# smile.net
KiCad netlist of a schematic drawn in EAGLE
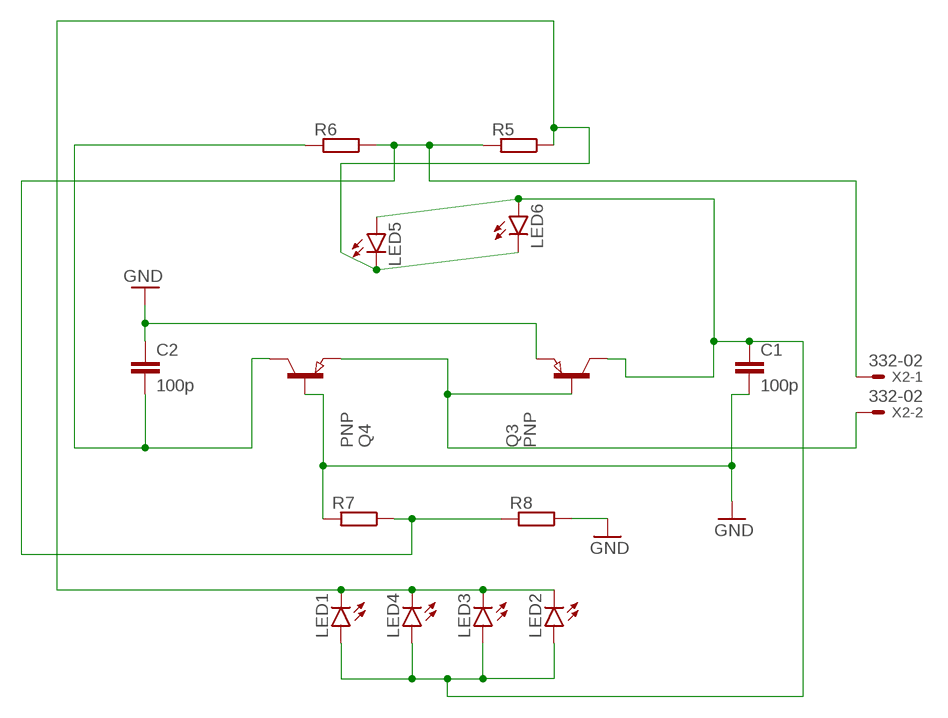
[diagram p0: schematic, sheet 1]

(export (version "E")
  (design (tool "Eeschema 10.0.6"))
  (components
    (comp (ref "C1")
      (value "100p")
      (footprint "eagle-import:C0805")
      (libsource (lib "eagle-import") (part "C-EUC0805"))
    )
    (comp (ref "C2")
      (value "100p")
      (footprint "eagle-import:C0805")
      (libsource (lib "eagle-import") (part "C-EUC0805"))
    )
    (comp (ref "LED1")
      (value "LEDCHIPLED_1206")
      (footprint "eagle-import:CHIPLED_1206")
      (libsource (lib "eagle-import") (part "LEDCHIPLED_1206"))
    )
    (comp (ref "LED2")
      (value "LEDCHIPLED_1206")
      (footprint "eagle-import:CHIPLED_1206")
      (libsource (lib "eagle-import") (part "LEDCHIPLED_1206"))
    )
    (comp (ref "LED3")
      (value "LEDCHIPLED_1206")
      (footprint "eagle-import:CHIPLED_1206")
      (libsource (lib "eagle-import") (part "LEDCHIPLED_1206"))
    )
    (comp (ref "LED4")
      (value "LEDCHIPLED_1206")
      (footprint "eagle-import:CHIPLED_1206")
      (libsource (lib "eagle-import") (part "LEDCHIPLED_1206"))
    )
    (comp (ref "LED5")
      (value "LEDCHIPLED_1206")
      (footprint "eagle-import:CHIPLED_1206")
      (libsource (lib "eagle-import") (part "LEDCHIPLED_1206"))
    )
    (comp (ref "LED6")
      (value "LEDCHIPLED_1206")
      (footprint "eagle-import:CHIPLED_1206")
      (libsource (lib "eagle-import") (part "LEDCHIPLED_1206"))
    )
    (comp (ref "Q3")
      (value "PNP")
      (footprint "eagle-import:SOT23")
      (libsource (lib "eagle-import") (part "PNP-TRANSISTOR_SOT23"))
    )
    (comp (ref "Q4")
      (value "PNP")
      (footprint "eagle-import:SOT23")
      (libsource (lib "eagle-import") (part "PNP-TRANSISTOR_SOT23"))
    )
    (comp (ref "R5")
      (value "SMK")
      (footprint "eagle-import:SMK")
      (libsource (lib "eagle-import") (part "SMK"))
    )
    (comp (ref "R6")
      (value "SMK")
      (footprint "eagle-import:SMK")
      (libsource (lib "eagle-import") (part "SMK"))
    )
    (comp (ref "R7")
      (value "SMK")
      (footprint "eagle-import:SMK")
      (libsource (lib "eagle-import") (part "SMK"))
    )
    (comp (ref "R8")
      (value "SMK")
      (footprint "eagle-import:SMK")
      (libsource (lib "eagle-import") (part "SMK"))
    )
    (comp (ref "X2")
      (value "332-02")
      (footprint "eagle-import:332-02")
      (libsource (lib "eagle-import") (part "332-02"))
    )
  )
  (nets
    (net (code "1") (name "GND") (class "Default")
      (node (ref "C1") (pin "2") (pinfunction "2_2") (pintype "passive"))
      (node (ref "C2") (pin "1") (pinfunction "1_1") (pintype "passive"))
      (node (ref "Q3") (pin "2") (pinfunction "E_2") (pintype "passive"))
      (node (ref "Q4") (pin "1") (pinfunction "B_1") (pintype "passive"))
      (node (ref "R7") (pin "2") (pinfunction "2_2") (pintype "passive"))
      (node (ref "R8") (pin "1") (pinfunction "1_1") (pintype "passive"))
    )
    (net (code "2") (name "Net-(LED1-PadC)") (class "Default")
      (node (ref "LED1") (pin "C") (pinfunction "C_C") (pintype "passive"))
      (node (ref "LED2") (pin "C") (pinfunction "C_C") (pintype "passive"))
      (node (ref "LED3") (pin "C") (pinfunction "C_C") (pintype "passive"))
      (node (ref "LED4") (pin "C") (pinfunction "C_C") (pintype "passive"))
      (node (ref "LED5") (pin "C") (pinfunction "C_C") (pintype "passive"))
      (node (ref "LED6") (pin "C") (pinfunction "C_C") (pintype "passive"))
      (node (ref "R5") (pin "1") (pinfunction "1_1") (pintype "passive"))
    )
    (net (code "3") (name "Net-(Q3-B)") (class "Default")
      (node (ref "Q3") (pin "1") (pinfunction "B_1") (pintype "passive"))
      (node (ref "Q4") (pin "2") (pinfunction "E_2") (pintype "passive"))
      (node (ref "X2") (pin "2") (pinfunction "S_2") (pintype "passive"))
    )
    (net (code "4") (name "Net-(Q3-C)") (class "Default")
      (node (ref "C1") (pin "1") (pinfunction "1_1") (pintype "passive"))
      (node (ref "LED1") (pin "A") (pinfunction "A_A") (pintype "passive"))
      (node (ref "LED2") (pin "A") (pinfunction "A_A") (pintype "passive"))
      (node (ref "LED3") (pin "A") (pinfunction "A_A") (pintype "passive"))
      (node (ref "LED4") (pin "A") (pinfunction "A_A") (pintype "passive"))
      (node (ref "LED5") (pin "A") (pinfunction "A_A") (pintype "passive"))
      (node (ref "LED6") (pin "A") (pinfunction "A_A") (pintype "passive"))
      (node (ref "Q3") (pin "3") (pinfunction "C_3") (pintype "passive"))
    )
    (net (code "5") (name "Net-(Q4-C)") (class "Default")
      (node (ref "C2") (pin "2") (pinfunction "2_2") (pintype "passive"))
      (node (ref "Q4") (pin "3") (pinfunction "C_3") (pintype "passive"))
      (node (ref "R6") (pin "2") (pinfunction "2_2") (pintype "passive"))
    )
    (net (code "6") (name "Net-(X2A-S)") (class "Default")
      (node (ref "R5") (pin "2") (pinfunction "2_2") (pintype "passive"))
      (node (ref "R6") (pin "1") (pinfunction "1_1") (pintype "passive"))
      (node (ref "R7") (pin "1") (pinfunction "1_1") (pintype "passive"))
      (node (ref "R8") (pin "2") (pinfunction "2_2") (pintype "passive"))
      (node (ref "X2") (pin "1") (pinfunction "S_1") (pintype "passive"))
    )
  )
)
